# LEDs.net
KiCad netlist of a schematic drawn in Altium Designer
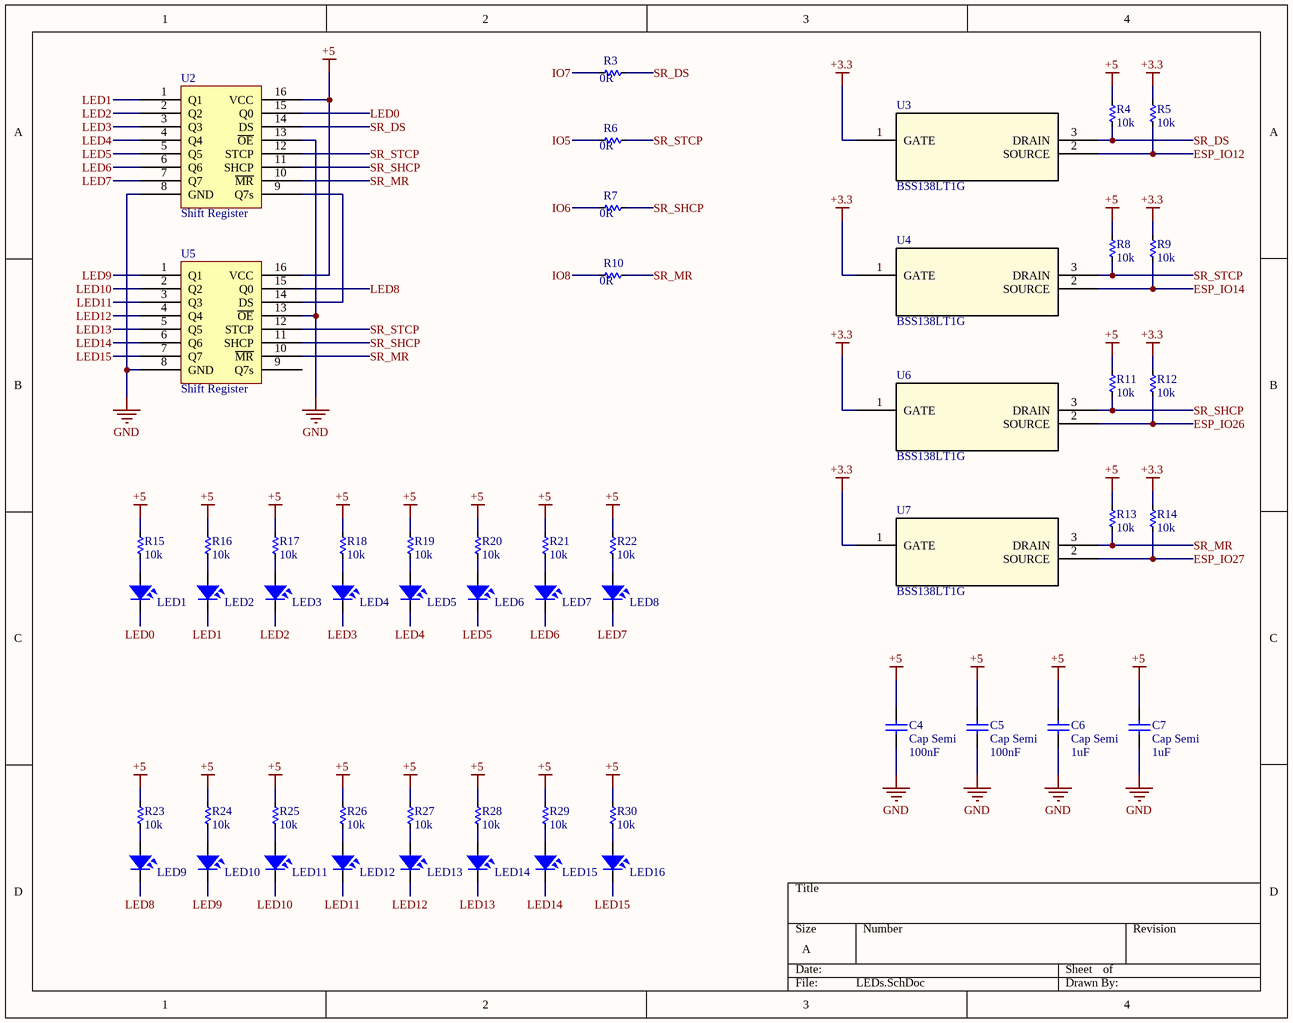
[diagram p0: LEDs.SchDoc]

(export (version "E")
  (design (tool "Eeschema 10.0.6"))
  (components
    (comp (ref "C4")
      (value "Cap Semi")
      (footprint "1608[0603]")
      (description "Capacitor (Semiconductor SIM Model)")
      (fields (field (name "ALTIUM_VALUE") "100nF") (field (name "PUBLISHER") "Altium Limited"))
      (libsource (lib "Miscellaneous Devices") (part "Cap Semi"))
    )
    (comp (ref "C5")
      (value "Cap Semi")
      (footprint "1608[0603]")
      (description "Capacitor (Semiconductor SIM Model)")
      (fields (field (name "ALTIUM_VALUE") "100nF") (field (name "PUBLISHER") "Altium Limited"))
      (libsource (lib "Miscellaneous Devices") (part "Cap Semi"))
    )
    (comp (ref "C6")
      (value "Cap Semi")
      (footprint "1608[0603]")
      (description "Capacitor (Semiconductor SIM Model)")
      (fields (field (name "ALTIUM_VALUE") "1uF") (field (name "PUBLISHER") "Altium Limited"))
      (libsource (lib "Miscellaneous Devices") (part "Cap Semi"))
    )
    (comp (ref "C7")
      (value "Cap Semi")
      (footprint "1608[0603]")
      (description "Capacitor (Semiconductor SIM Model)")
      (fields (field (name "ALTIUM_VALUE") "1uF") (field (name "PUBLISHER") "Altium Limited"))
      (libsource (lib "Miscellaneous Devices") (part "Cap Semi"))
    )
    (comp (ref "LED1") (value "LED") (footprint "LED-0805-Red") (libsource (lib "LIBRARY") (part "LED SMD")))
    (comp (ref "LED2") (value "LED") (footprint "LED-0805-Red") (libsource (lib "LIBRARY") (part "LED SMD")))
    (comp (ref "LED3") (value "LED") (footprint "LED-0805-Red") (libsource (lib "LIBRARY") (part "LED SMD")))
    (comp (ref "LED4") (value "LED") (footprint "LED-0805-Red") (libsource (lib "LIBRARY") (part "LED SMD")))
    (comp (ref "LED5") (value "LED") (footprint "LED-0805-Red") (libsource (lib "LIBRARY") (part "LED SMD")))
    (comp (ref "LED6") (value "LED") (footprint "LED-0805-Red") (libsource (lib "LIBRARY") (part "LED SMD")))
    (comp (ref "LED7") (value "LED") (footprint "LED-0805-Red") (libsource (lib "LIBRARY") (part "LED SMD")))
    (comp (ref "LED8") (value "LED") (footprint "LED-0805-Red") (libsource (lib "LIBRARY") (part "LED SMD")))
    (comp (ref "LED9") (value "LED") (footprint "LED-0805-Red") (libsource (lib "LIBRARY") (part "LED SMD")))
    (comp (ref "LED10") (value "LED") (footprint "LED-0805-Red") (libsource (lib "LIBRARY") (part "LED SMD")))
    (comp (ref "LED11") (value "LED") (footprint "LED-0805-Red") (libsource (lib "LIBRARY") (part "LED SMD")))
    (comp (ref "LED12") (value "LED") (footprint "LED-0805-Red") (libsource (lib "LIBRARY") (part "LED SMD")))
    (comp (ref "LED13") (value "LED") (footprint "LED-0805-Red") (libsource (lib "LIBRARY") (part "LED SMD")))
    (comp (ref "LED14") (value "LED") (footprint "LED-0805-Red") (libsource (lib "LIBRARY") (part "LED SMD")))
    (comp (ref "LED15") (value "LED") (footprint "LED-0805-Red") (libsource (lib "LIBRARY") (part "LED SMD")))
    (comp (ref "LED16") (value "LED") (footprint "LED-0805-Red") (libsource (lib "LIBRARY") (part "LED SMD")))
    (comp (ref "R3")
      (value "0R")
      (footprint "RES-SMD-0603")
      (description "Resistor")
      (fields
        (field (name "MANUFACTURER") "Generic Components")
        (field (name "Comment") "Res")
        (field (name "PUBLISHER") "Altium Hobart Technology Centre")
      )
      (libsource (lib "LIBRARY") (part "Res-SMD"))
    )
    (comp (ref "R4")
      (value "10k")
      (footprint "RES-SMD-0603")
      (description "Resistor")
      (fields
        (field (name "MANUFACTURER") "Generic Components")
        (field (name "Comment") "Res")
        (field (name "PUBLISHER") "Altium Hobart Technology Centre")
      )
      (libsource (lib "LIBRARY") (part "Res-SMD"))
    )
    (comp (ref "R5")
      (value "10k")
      (footprint "RES-SMD-0603")
      (description "Resistor")
      (fields
        (field (name "MANUFACTURER") "Generic Components")
        (field (name "Comment") "Res")
        (field (name "PUBLISHER") "Altium Hobart Technology Centre")
      )
      (libsource (lib "LIBRARY") (part "Res-SMD"))
    )
    (comp (ref "R6")
      (value "0R")
      (footprint "RES-SMD-0603")
      (description "Resistor")
      (fields
        (field (name "MANUFACTURER") "Generic Components")
        (field (name "Comment") "Res")
        (field (name "PUBLISHER") "Altium Hobart Technology Centre")
      )
      (libsource (lib "LIBRARY") (part "Res-SMD"))
    )
    (comp (ref "R7")
      (value "0R")
      (footprint "RES-SMD-0603")
      (description "Resistor")
      (fields
        (field (name "MANUFACTURER") "Generic Components")
        (field (name "Comment") "Res")
        (field (name "PUBLISHER") "Altium Hobart Technology Centre")
      )
      (libsource (lib "LIBRARY") (part "Res-SMD"))
    )
    (comp (ref "R8")
      (value "10k")
      (footprint "RES-SMD-0603")
      (description "Resistor")
      (fields
        (field (name "MANUFACTURER") "Generic Components")
        (field (name "Comment") "Res")
        (field (name "PUBLISHER") "Altium Hobart Technology Centre")
      )
      (libsource (lib "LIBRARY") (part "Res-SMD"))
    )
    (comp (ref "R9")
      (value "10k")
      (footprint "RES-SMD-0603")
      (description "Resistor")
      (fields
        (field (name "MANUFACTURER") "Generic Components")
        (field (name "Comment") "Res")
        (field (name "PUBLISHER") "Altium Hobart Technology Centre")
      )
      (libsource (lib "LIBRARY") (part "Res-SMD"))
    )
    (comp (ref "R10")
      (value "0R")
      (footprint "RES-SMD-0603")
      (description "Resistor")
      (fields
        (field (name "MANUFACTURER") "Generic Components")
        (field (name "Comment") "Res")
        (field (name "PUBLISHER") "Altium Hobart Technology Centre")
      )
      (libsource (lib "LIBRARY") (part "Res-SMD"))
    )
    (comp (ref "R11")
      (value "10k")
      (footprint "RES-SMD-0603")
      (description "Resistor")
      (fields
        (field (name "MANUFACTURER") "Generic Components")
        (field (name "Comment") "Res")
        (field (name "PUBLISHER") "Altium Hobart Technology Centre")
      )
      (libsource (lib "LIBRARY") (part "Res-SMD"))
    )
    (comp (ref "R12")
      (value "10k")
      (footprint "RES-SMD-0603")
      (description "Resistor")
      (fields
        (field (name "MANUFACTURER") "Generic Components")
        (field (name "Comment") "Res")
        (field (name "PUBLISHER") "Altium Hobart Technology Centre")
      )
      (libsource (lib "LIBRARY") (part "Res-SMD"))
    )
    (comp (ref "R13")
      (value "10k")
      (footprint "RES-SMD-0603")
      (description "Resistor")
      (fields
        (field (name "MANUFACTURER") "Generic Components")
        (field (name "Comment") "Res")
        (field (name "PUBLISHER") "Altium Hobart Technology Centre")
      )
      (libsource (lib "LIBRARY") (part "Res-SMD"))
    )
    (comp (ref "R14")
      (value "10k")
      (footprint "RES-SMD-0603")
      (description "Resistor")
      (fields
        (field (name "MANUFACTURER") "Generic Components")
        (field (name "Comment") "Res")
        (field (name "PUBLISHER") "Altium Hobart Technology Centre")
      )
      (libsource (lib "LIBRARY") (part "Res-SMD"))
    )
    (comp (ref "R15")
      (value "10k")
      (footprint "RES-SMD-0603")
      (description "Resistor")
      (fields
        (field (name "MANUFACTURER") "Generic Components")
        (field (name "Comment") "Res")
        (field (name "PUBLISHER") "Altium Hobart Technology Centre")
      )
      (libsource (lib "LIBRARY") (part "Res-SMD"))
    )
    (comp (ref "R16")
      (value "10k")
      (footprint "RES-SMD-0603")
      (description "Resistor")
      (fields
        (field (name "MANUFACTURER") "Generic Components")
        (field (name "Comment") "Res")
        (field (name "PUBLISHER") "Altium Hobart Technology Centre")
      )
      (libsource (lib "LIBRARY") (part "Res-SMD"))
    )
    (comp (ref "R17")
      (value "10k")
      (footprint "RES-SMD-0603")
      (description "Resistor")
      (fields
        (field (name "MANUFACTURER") "Generic Components")
        (field (name "Comment") "Res")
        (field (name "PUBLISHER") "Altium Hobart Technology Centre")
      )
      (libsource (lib "LIBRARY") (part "Res-SMD"))
    )
    (comp (ref "R18")
      (value "10k")
      (footprint "RES-SMD-0603")
      (description "Resistor")
      (fields
        (field (name "MANUFACTURER") "Generic Components")
        (field (name "Comment") "Res")
        (field (name "PUBLISHER") "Altium Hobart Technology Centre")
      )
      (libsource (lib "LIBRARY") (part "Res-SMD"))
    )
    (comp (ref "R19")
      (value "10k")
      (footprint "RES-SMD-0603")
      (description "Resistor")
      (fields
        (field (name "MANUFACTURER") "Generic Components")
        (field (name "Comment") "Res")
        (field (name "PUBLISHER") "Altium Hobart Technology Centre")
      )
      (libsource (lib "LIBRARY") (part "Res-SMD"))
    )
    (comp (ref "R20")
      (value "10k")
      (footprint "RES-SMD-0603")
      (description "Resistor")
      (fields
        (field (name "MANUFACTURER") "Generic Components")
        (field (name "Comment") "Res")
        (field (name "PUBLISHER") "Altium Hobart Technology Centre")
      )
      (libsource (lib "LIBRARY") (part "Res-SMD"))
    )
    (comp (ref "R21")
      (value "10k")
      (footprint "RES-SMD-0603")
      (description "Resistor")
      (fields
        (field (name "MANUFACTURER") "Generic Components")
        (field (name "Comment") "Res")
        (field (name "PUBLISHER") "Altium Hobart Technology Centre")
      )
      (libsource (lib "LIBRARY") (part "Res-SMD"))
    )
    (comp (ref "R22")
      (value "10k")
      (footprint "RES-SMD-0603")
      (description "Resistor")
      (fields
        (field (name "MANUFACTURER") "Generic Components")
        (field (name "Comment") "Res")
        (field (name "PUBLISHER") "Altium Hobart Technology Centre")
      )
      (libsource (lib "LIBRARY") (part "Res-SMD"))
    )
    (comp (ref "R23")
      (value "10k")
      (footprint "RES-SMD-0603")
      (description "Resistor")
      (fields
        (field (name "MANUFACTURER") "Generic Components")
        (field (name "Comment") "Res")
        (field (name "PUBLISHER") "Altium Hobart Technology Centre")
      )
      (libsource (lib "LIBRARY") (part "Res-SMD"))
    )
    (comp (ref "R24")
      (value "10k")
      (footprint "RES-SMD-0603")
      (description "Resistor")
      (fields
        (field (name "MANUFACTURER") "Generic Components")
        (field (name "Comment") "Res")
        (field (name "PUBLISHER") "Altium Hobart Technology Centre")
      )
      (libsource (lib "LIBRARY") (part "Res-SMD"))
    )
    (comp (ref "R25")
      (value "10k")
      (footprint "RES-SMD-0603")
      (description "Resistor")
      (fields
        (field (name "MANUFACTURER") "Generic Components")
        (field (name "Comment") "Res")
        (field (name "PUBLISHER") "Altium Hobart Technology Centre")
      )
      (libsource (lib "LIBRARY") (part "Res-SMD"))
    )
    (comp (ref "R26")
      (value "10k")
      (footprint "RES-SMD-0603")
      (description "Resistor")
      (fields
        (field (name "MANUFACTURER") "Generic Components")
        (field (name "Comment") "Res")
        (field (name "PUBLISHER") "Altium Hobart Technology Centre")
      )
      (libsource (lib "LIBRARY") (part "Res-SMD"))
    )
    (comp (ref "R27")
      (value "10k")
      (footprint "RES-SMD-0603")
      (description "Resistor")
      (fields
        (field (name "MANUFACTURER") "Generic Components")
        (field (name "Comment") "Res")
        (field (name "PUBLISHER") "Altium Hobart Technology Centre")
      )
      (libsource (lib "LIBRARY") (part "Res-SMD"))
    )
    (comp (ref "R28")
      (value "10k")
      (footprint "RES-SMD-0603")
      (description "Resistor")
      (fields
        (field (name "MANUFACTURER") "Generic Components")
        (field (name "Comment") "Res")
        (field (name "PUBLISHER") "Altium Hobart Technology Centre")
      )
      (libsource (lib "LIBRARY") (part "Res-SMD"))
    )
    (comp (ref "R29")
      (value "10k")
      (footprint "RES-SMD-0603")
      (description "Resistor")
      (fields
        (field (name "MANUFACTURER") "Generic Components")
        (field (name "Comment") "Res")
        (field (name "PUBLISHER") "Altium Hobart Technology Centre")
      )
      (libsource (lib "LIBRARY") (part "Res-SMD"))
    )
    (comp (ref "R30")
      (value "10k")
      (footprint "RES-SMD-0603")
      (description "Resistor")
      (fields
        (field (name "MANUFACTURER") "Generic Components")
        (field (name "Comment") "Res")
        (field (name "PUBLISHER") "Altium Hobart Technology Centre")
      )
      (libsource (lib "LIBRARY") (part "Res-SMD"))
    )
    (comp (ref "U2")
      (value "Shift Register")
      (footprint "SO16")
      (description "74HC Shift Register SOIC-16_150mil Registers ROHS")
      (libsource (lib "74HC595") (part "74HC595"))
    )
    (comp (ref "U3")
      (value "BSS138LT1G")
      (footprint "SOT23-3_ONS")
      (description "No Description Available")
      (fields (field (name "COPYRIGHT") "Copyright (C) 2018 Accelerated Designs. All rights reserved"))
      (libsource (lib "BSS138LT1G") (part "BSS138LT1G"))
    )
    (comp (ref "U4")
      (value "BSS138LT1G")
      (footprint "SOT23-3_ONS")
      (description "No Description Available")
      (fields (field (name "COPYRIGHT") "Copyright (C) 2018 Accelerated Designs. All rights reserved"))
      (libsource (lib "BSS138LT1G") (part "BSS138LT1G"))
    )
    (comp (ref "U5")
      (value "Shift Register")
      (footprint "SO16")
      (description "74HC Shift Register SOIC-16_150mil Registers ROHS")
      (libsource (lib "74HC595") (part "74HC595"))
    )
    (comp (ref "U6")
      (value "BSS138LT1G")
      (footprint "SOT23-3_ONS")
      (description "No Description Available")
      (fields (field (name "COPYRIGHT") "Copyright (C) 2018 Accelerated Designs. All rights reserved"))
      (libsource (lib "BSS138LT1G") (part "BSS138LT1G"))
    )
    (comp (ref "U7")
      (value "BSS138LT1G")
      (footprint "SOT23-3_ONS")
      (description "No Description Available")
      (fields (field (name "COPYRIGHT") "Copyright (C) 2018 Accelerated Designs. All rights reserved"))
      (libsource (lib "BSS138LT1G") (part "BSS138LT1G"))
    )
  )
  (nets
    (net (code "1") (name "+3.3") (class "Default")
      (node (ref "R12") (pin "1") (pinfunction "1_1") (pintype "passive"))
      (node (ref "R14") (pin "1") (pinfunction "1_1") (pintype "passive"))
      (node (ref "R5") (pin "1") (pinfunction "1_1") (pintype "passive"))
      (node (ref "R9") (pin "1") (pinfunction "1_1") (pintype "passive"))
      (node (ref "U3") (pin "1") (pinfunction "GATE_1") (pintype "passive"))
      (node (ref "U4") (pin "1") (pinfunction "GATE_1") (pintype "passive"))
      (node (ref "U6") (pin "1") (pinfunction "GATE_1") (pintype "passive"))
      (node (ref "U7") (pin "1") (pinfunction "GATE_1") (pintype "passive"))
    )
    (net (code "2") (name "+5") (class "Default")
      (node (ref "C4") (pin "1") (pinfunction "1_1") (pintype "passive"))
      (node (ref "C5") (pin "1") (pinfunction "1_1") (pintype "passive"))
      (node (ref "C6") (pin "1") (pinfunction "1_1") (pintype "passive"))
      (node (ref "C7") (pin "1") (pinfunction "1_1") (pintype "passive"))
      (node (ref "R11") (pin "1") (pinfunction "1_1") (pintype "passive"))
      (node (ref "R13") (pin "1") (pinfunction "1_1") (pintype "passive"))
      (node (ref "R15") (pin "1") (pinfunction "1_1") (pintype "passive"))
      (node (ref "R16") (pin "1") (pinfunction "1_1") (pintype "passive"))
      (node (ref "R17") (pin "1") (pinfunction "1_1") (pintype "passive"))
      (node (ref "R18") (pin "1") (pinfunction "1_1") (pintype "passive"))
      (node (ref "R19") (pin "1") (pinfunction "1_1") (pintype "passive"))
      (node (ref "R20") (pin "1") (pinfunction "1_1") (pintype "passive"))
      (node (ref "R21") (pin "1") (pinfunction "1_1") (pintype "passive"))
      (node (ref "R22") (pin "1") (pinfunction "1_1") (pintype "passive"))
      (node (ref "R23") (pin "1") (pinfunction "1_1") (pintype "passive"))
      (node (ref "R24") (pin "1") (pinfunction "1_1") (pintype "passive"))
      (node (ref "R25") (pin "1") (pinfunction "1_1") (pintype "passive"))
      (node (ref "R26") (pin "1") (pinfunction "1_1") (pintype "passive"))
      (node (ref "R27") (pin "1") (pinfunction "1_1") (pintype "passive"))
      (node (ref "R28") (pin "1") (pinfunction "1_1") (pintype "passive"))
      (node (ref "R29") (pin "1") (pinfunction "1_1") (pintype "passive"))
      (node (ref "R30") (pin "1") (pinfunction "1_1") (pintype "passive"))
      (node (ref "R4") (pin "1") (pinfunction "1_1") (pintype "passive"))
      (node (ref "R8") (pin "1") (pinfunction "1_1") (pintype "passive"))
      (node (ref "U2") (pin "16") (pinfunction "VCC_16") (pintype "passive"))
      (node (ref "U5") (pin "16") (pinfunction "VCC_16") (pintype "passive"))
    )
    (net (code "3") (name "/ESP_IO12") (class "Default")
      (node (ref "R5") (pin "2") (pinfunction "2_2") (pintype "passive"))
      (node (ref "U3") (pin "2") (pinfunction "SOURCE_2") (pintype "passive"))
    )
    (net (code "4") (name "/ESP_IO14") (class "Default")
      (node (ref "R9") (pin "2") (pinfunction "2_2") (pintype "passive"))
      (node (ref "U4") (pin "2") (pinfunction "SOURCE_2") (pintype "passive"))
    )
    (net (code "5") (name "/ESP_IO26") (class "Default")
      (node (ref "R12") (pin "2") (pinfunction "2_2") (pintype "passive"))
      (node (ref "U6") (pin "2") (pinfunction "SOURCE_2") (pintype "passive"))
    )
    (net (code "6") (name "/ESP_IO27") (class "Default")
      (node (ref "R14") (pin "2") (pinfunction "2_2") (pintype "passive"))
      (node (ref "U7") (pin "2") (pinfunction "SOURCE_2") (pintype "passive"))
    )
    (net (code "7") (name "/IO5") (class "Default")
      (node (ref "R6") (pin "2") (pinfunction "2_2") (pintype "passive"))
    )
    (net (code "8") (name "/IO6") (class "Default")
      (node (ref "R7") (pin "2") (pinfunction "2_2") (pintype "passive"))
    )
    (net (code "9") (name "/IO7") (class "Default")
      (node (ref "R3") (pin "2") (pinfunction "2_2") (pintype "passive"))
    )
    (net (code "10") (name "/IO8") (class "Default")
      (node (ref "R10") (pin "2") (pinfunction "2_2") (pintype "passive"))
    )
    (net (code "11") (name "/LED0") (class "Default")
      (node (ref "LED1") (pin "2") (pinfunction "2_2") (pintype "passive"))
      (node (ref "U2") (pin "15") (pinfunction "Q0_15") (pintype "passive"))
    )
    (net (code "12") (name "/LED1") (class "Default")
      (node (ref "LED2") (pin "2") (pinfunction "2_2") (pintype "passive"))
      (node (ref "U2") (pin "1") (pinfunction "Q1_1") (pintype "passive"))
    )
    (net (code "13") (name "/LED2") (class "Default")
      (node (ref "LED3") (pin "2") (pinfunction "2_2") (pintype "passive"))
      (node (ref "U2") (pin "2") (pinfunction "Q2_2") (pintype "passive"))
    )
    (net (code "14") (name "/LED3") (class "Default")
      (node (ref "LED4") (pin "2") (pinfunction "2_2") (pintype "passive"))
      (node (ref "U2") (pin "3") (pinfunction "Q3_3") (pintype "passive"))
    )
    (net (code "15") (name "/LED4") (class "Default")
      (node (ref "LED5") (pin "2") (pinfunction "2_2") (pintype "passive"))
      (node (ref "U2") (pin "4") (pinfunction "Q4_4") (pintype "passive"))
    )
    (net (code "16") (name "/LED5") (class "Default")
      (node (ref "LED6") (pin "2") (pinfunction "2_2") (pintype "passive"))
      (node (ref "U2") (pin "5") (pinfunction "Q5_5") (pintype "passive"))
    )
    (net (code "17") (name "/LED6") (class "Default")
      (node (ref "LED7") (pin "2") (pinfunction "2_2") (pintype "passive"))
      (node (ref "U2") (pin "6") (pinfunction "Q6_6") (pintype "passive"))
    )
    (net (code "18") (name "/LED7") (class "Default")
      (node (ref "LED8") (pin "2") (pinfunction "2_2") (pintype "passive"))
      (node (ref "U2") (pin "7") (pinfunction "Q7_7") (pintype "passive"))
    )
    (net (code "19") (name "/LED8") (class "Default")
      (node (ref "LED9") (pin "2") (pinfunction "2_2") (pintype "passive"))
      (node (ref "U5") (pin "15") (pinfunction "Q0_15") (pintype "passive"))
    )
    (net (code "20") (name "/LED9") (class "Default")
      (node (ref "LED10") (pin "2") (pinfunction "2_2") (pintype "passive"))
      (node (ref "U5") (pin "1") (pinfunction "Q1_1") (pintype "passive"))
    )
    (net (code "21") (name "/LED10") (class "Default")
      (node (ref "LED11") (pin "2") (pinfunction "2_2") (pintype "passive"))
      (node (ref "U5") (pin "2") (pinfunction "Q2_2") (pintype "passive"))
    )
    (net (code "22") (name "/LED11") (class "Default")
      (node (ref "LED12") (pin "2") (pinfunction "2_2") (pintype "passive"))
      (node (ref "U5") (pin "3") (pinfunction "Q3_3") (pintype "passive"))
    )
    (net (code "23") (name "/LED12") (class "Default")
      (node (ref "LED13") (pin "2") (pinfunction "2_2") (pintype "passive"))
      (node (ref "U5") (pin "4") (pinfunction "Q4_4") (pintype "passive"))
    )
    (net (code "24") (name "/LED13") (class "Default")
      (node (ref "LED14") (pin "2") (pinfunction "2_2") (pintype "passive"))
      (node (ref "U5") (pin "5") (pinfunction "Q5_5") (pintype "passive"))
    )
    (net (code "25") (name "/LED14") (class "Default")
      (node (ref "LED15") (pin "2") (pinfunction "2_2") (pintype "passive"))
      (node (ref "U5") (pin "6") (pinfunction "Q6_6") (pintype "passive"))
    )
    (net (code "26") (name "/LED15") (class "Default")
      (node (ref "LED16") (pin "2") (pinfunction "2_2") (pintype "passive"))
      (node (ref "U5") (pin "7") (pinfunction "Q7_7") (pintype "passive"))
    )
    (net (code "27") (name "/SR_DS") (class "Default")
      (node (ref "R3") (pin "1") (pinfunction "1_1") (pintype "passive"))
      (node (ref "R4") (pin "2") (pinfunction "2_2") (pintype "passive"))
      (node (ref "U2") (pin "14") (pinfunction "DS_14") (pintype "passive"))
      (node (ref "U3") (pin "3") (pinfunction "DRAIN_3") (pintype "passive"))
    )
    (net (code "28") (name "/SR_MR") (class "Default")
      (node (ref "R10") (pin "1") (pinfunction "1_1") (pintype "passive"))
      (node (ref "R13") (pin "2") (pinfunction "2_2") (pintype "passive"))
      (node (ref "U2") (pin "10") (pinfunction "~{MR}_10") (pintype "passive"))
      (node (ref "U5") (pin "10") (pinfunction "~{MR}_10") (pintype "passive"))
      (node (ref "U7") (pin "3") (pinfunction "DRAIN_3") (pintype "passive"))
    )
    (net (code "29") (name "/SR_SHCP") (class "Default")
      (node (ref "R11") (pin "2") (pinfunction "2_2") (pintype "passive"))
      (node (ref "R7") (pin "1") (pinfunction "1_1") (pintype "passive"))
      (node (ref "U2") (pin "11") (pinfunction "SHCP_11") (pintype "passive"))
      (node (ref "U5") (pin "11") (pinfunction "SHCP_11") (pintype "passive"))
      (node (ref "U6") (pin "3") (pinfunction "DRAIN_3") (pintype "passive"))
    )
    (net (code "30") (name "/SR_STCP") (class "Default")
      (node (ref "R6") (pin "1") (pinfunction "1_1") (pintype "passive"))
      (node (ref "R8") (pin "2") (pinfunction "2_2") (pintype "passive"))
      (node (ref "U2") (pin "12") (pinfunction "STCP_12") (pintype "passive"))
      (node (ref "U4") (pin "3") (pinfunction "DRAIN_3") (pintype "passive"))
      (node (ref "U5") (pin "12") (pinfunction "STCP_12") (pintype "passive"))
    )
    (net (code "31") (name "GND") (class "Default")
      (node (ref "C4") (pin "2") (pinfunction "2_2") (pintype "passive"))
      (node (ref "C5") (pin "2") (pinfunction "2_2") (pintype "passive"))
      (node (ref "C6") (pin "2") (pinfunction "2_2") (pintype "passive"))
      (node (ref "C7") (pin "2") (pinfunction "2_2") (pintype "passive"))
      (node (ref "U2") (pin "13") (pinfunction "~{OE}_13") (pintype "passive"))
      (node (ref "U2") (pin "8") (pinfunction "GND_8") (pintype "passive"))
      (node (ref "U5") (pin "13") (pinfunction "~{OE}_13") (pintype "passive"))
      (node (ref "U5") (pin "8") (pinfunction "GND_8") (pintype "passive"))
    )
    (net (code "32") (name "Net-(LED1-Pad1)") (class "Default")
      (node (ref "LED1") (pin "1") (pinfunction "1_1") (pintype "passive"))
      (node (ref "R15") (pin "2") (pinfunction "2_2") (pintype "passive"))
    )
    (net (code "33") (name "Net-(LED2-Pad1)") (class "Default")
      (node (ref "LED2") (pin "1") (pinfunction "1_1") (pintype "passive"))
      (node (ref "R16") (pin "2") (pinfunction "2_2") (pintype "passive"))
    )
    (net (code "34") (name "Net-(LED3-Pad1)") (class "Default")
      (node (ref "LED3") (pin "1") (pinfunction "1_1") (pintype "passive"))
      (node (ref "R17") (pin "2") (pinfunction "2_2") (pintype "passive"))
    )
    (net (code "35") (name "Net-(LED4-Pad1)") (class "Default")
      (node (ref "LED4") (pin "1") (pinfunction "1_1") (pintype "passive"))
      (node (ref "R18") (pin "2") (pinfunction "2_2") (pintype "passive"))
    )
    (net (code "36") (name "Net-(LED5-Pad1)") (class "Default")
      (node (ref "LED5") (pin "1") (pinfunction "1_1") (pintype "passive"))
      (node (ref "R19") (pin "2") (pinfunction "2_2") (pintype "passive"))
    )
    (net (code "37") (name "Net-(LED6-Pad1)") (class "Default")
      (node (ref "LED6") (pin "1") (pinfunction "1_1") (pintype "passive"))
      (node (ref "R20") (pin "2") (pinfunction "2_2") (pintype "passive"))
    )
    (net (code "38") (name "Net-(LED7-Pad1)") (class "Default")
      (node (ref "LED7") (pin "1") (pinfunction "1_1") (pintype "passive"))
      (node (ref "R21") (pin "2") (pinfunction "2_2") (pintype "passive"))
    )
    (net (code "39") (name "Net-(LED8-Pad1)") (class "Default")
      (node (ref "LED8") (pin "1") (pinfunction "1_1") (pintype "passive"))
      (node (ref "R22") (pin "2") (pinfunction "2_2") (pintype "passive"))
    )
    (net (code "40") (name "Net-(LED9-Pad1)") (class "Default")
      (node (ref "LED9") (pin "1") (pinfunction "1_1") (pintype "passive"))
      (node (ref "R23") (pin "2") (pinfunction "2_2") (pintype "passive"))
    )
    (net (code "41") (name "Net-(LED10-Pad1)") (class "Default")
      (node (ref "LED10") (pin "1") (pinfunction "1_1") (pintype "passive"))
      (node (ref "R24") (pin "2") (pinfunction "2_2") (pintype "passive"))
    )
    (net (code "42") (name "Net-(LED11-Pad1)") (class "Default")
      (node (ref "LED11") (pin "1") (pinfunction "1_1") (pintype "passive"))
      (node (ref "R25") (pin "2") (pinfunction "2_2") (pintype "passive"))
    )
    (net (code "43") (name "Net-(LED12-Pad1)") (class "Default")
      (node (ref "LED12") (pin "1") (pinfunction "1_1") (pintype "passive"))
      (node (ref "R26") (pin "2") (pinfunction "2_2") (pintype "passive"))
    )
    (net (code "44") (name "Net-(LED13-Pad1)") (class "Default")
      (node (ref "LED13") (pin "1") (pinfunction "1_1") (pintype "passive"))
      (node (ref "R27") (pin "2") (pinfunction "2_2") (pintype "passive"))
    )
    (net (code "45") (name "Net-(LED14-Pad1)") (class "Default")
      (node (ref "LED14") (pin "1") (pinfunction "1_1") (pintype "passive"))
      (node (ref "R28") (pin "2") (pinfunction "2_2") (pintype "passive"))
    )
    (net (code "46") (name "Net-(LED15-Pad1)") (class "Default")
      (node (ref "LED15") (pin "1") (pinfunction "1_1") (pintype "passive"))
      (node (ref "R29") (pin "2") (pinfunction "2_2") (pintype "passive"))
    )
    (net (code "47") (name "Net-(LED16-Pad1)") (class "Default")
      (node (ref "LED16") (pin "1") (pinfunction "1_1") (pintype "passive"))
      (node (ref "R30") (pin "2") (pinfunction "2_2") (pintype "passive"))
    )
    (net (code "48") (name "Net-(U2-Q7s)") (class "Default")
      (node (ref "U2") (pin "9") (pinfunction "Q7s_9") (pintype "passive"))
      (node (ref "U5") (pin "14") (pinfunction "DS_14") (pintype "passive"))
    )
    (net (code "49") (name "unconnected-(U5-Q7s-Pad9)") (class "Default")
      (node (ref "U5") (pin "9") (pinfunction "Q7s_9") (pintype "passive"))
    )
  )
)
